# STM32-Nucleo-144.net
KiCad netlist of a schematic drawn in Altium Designer
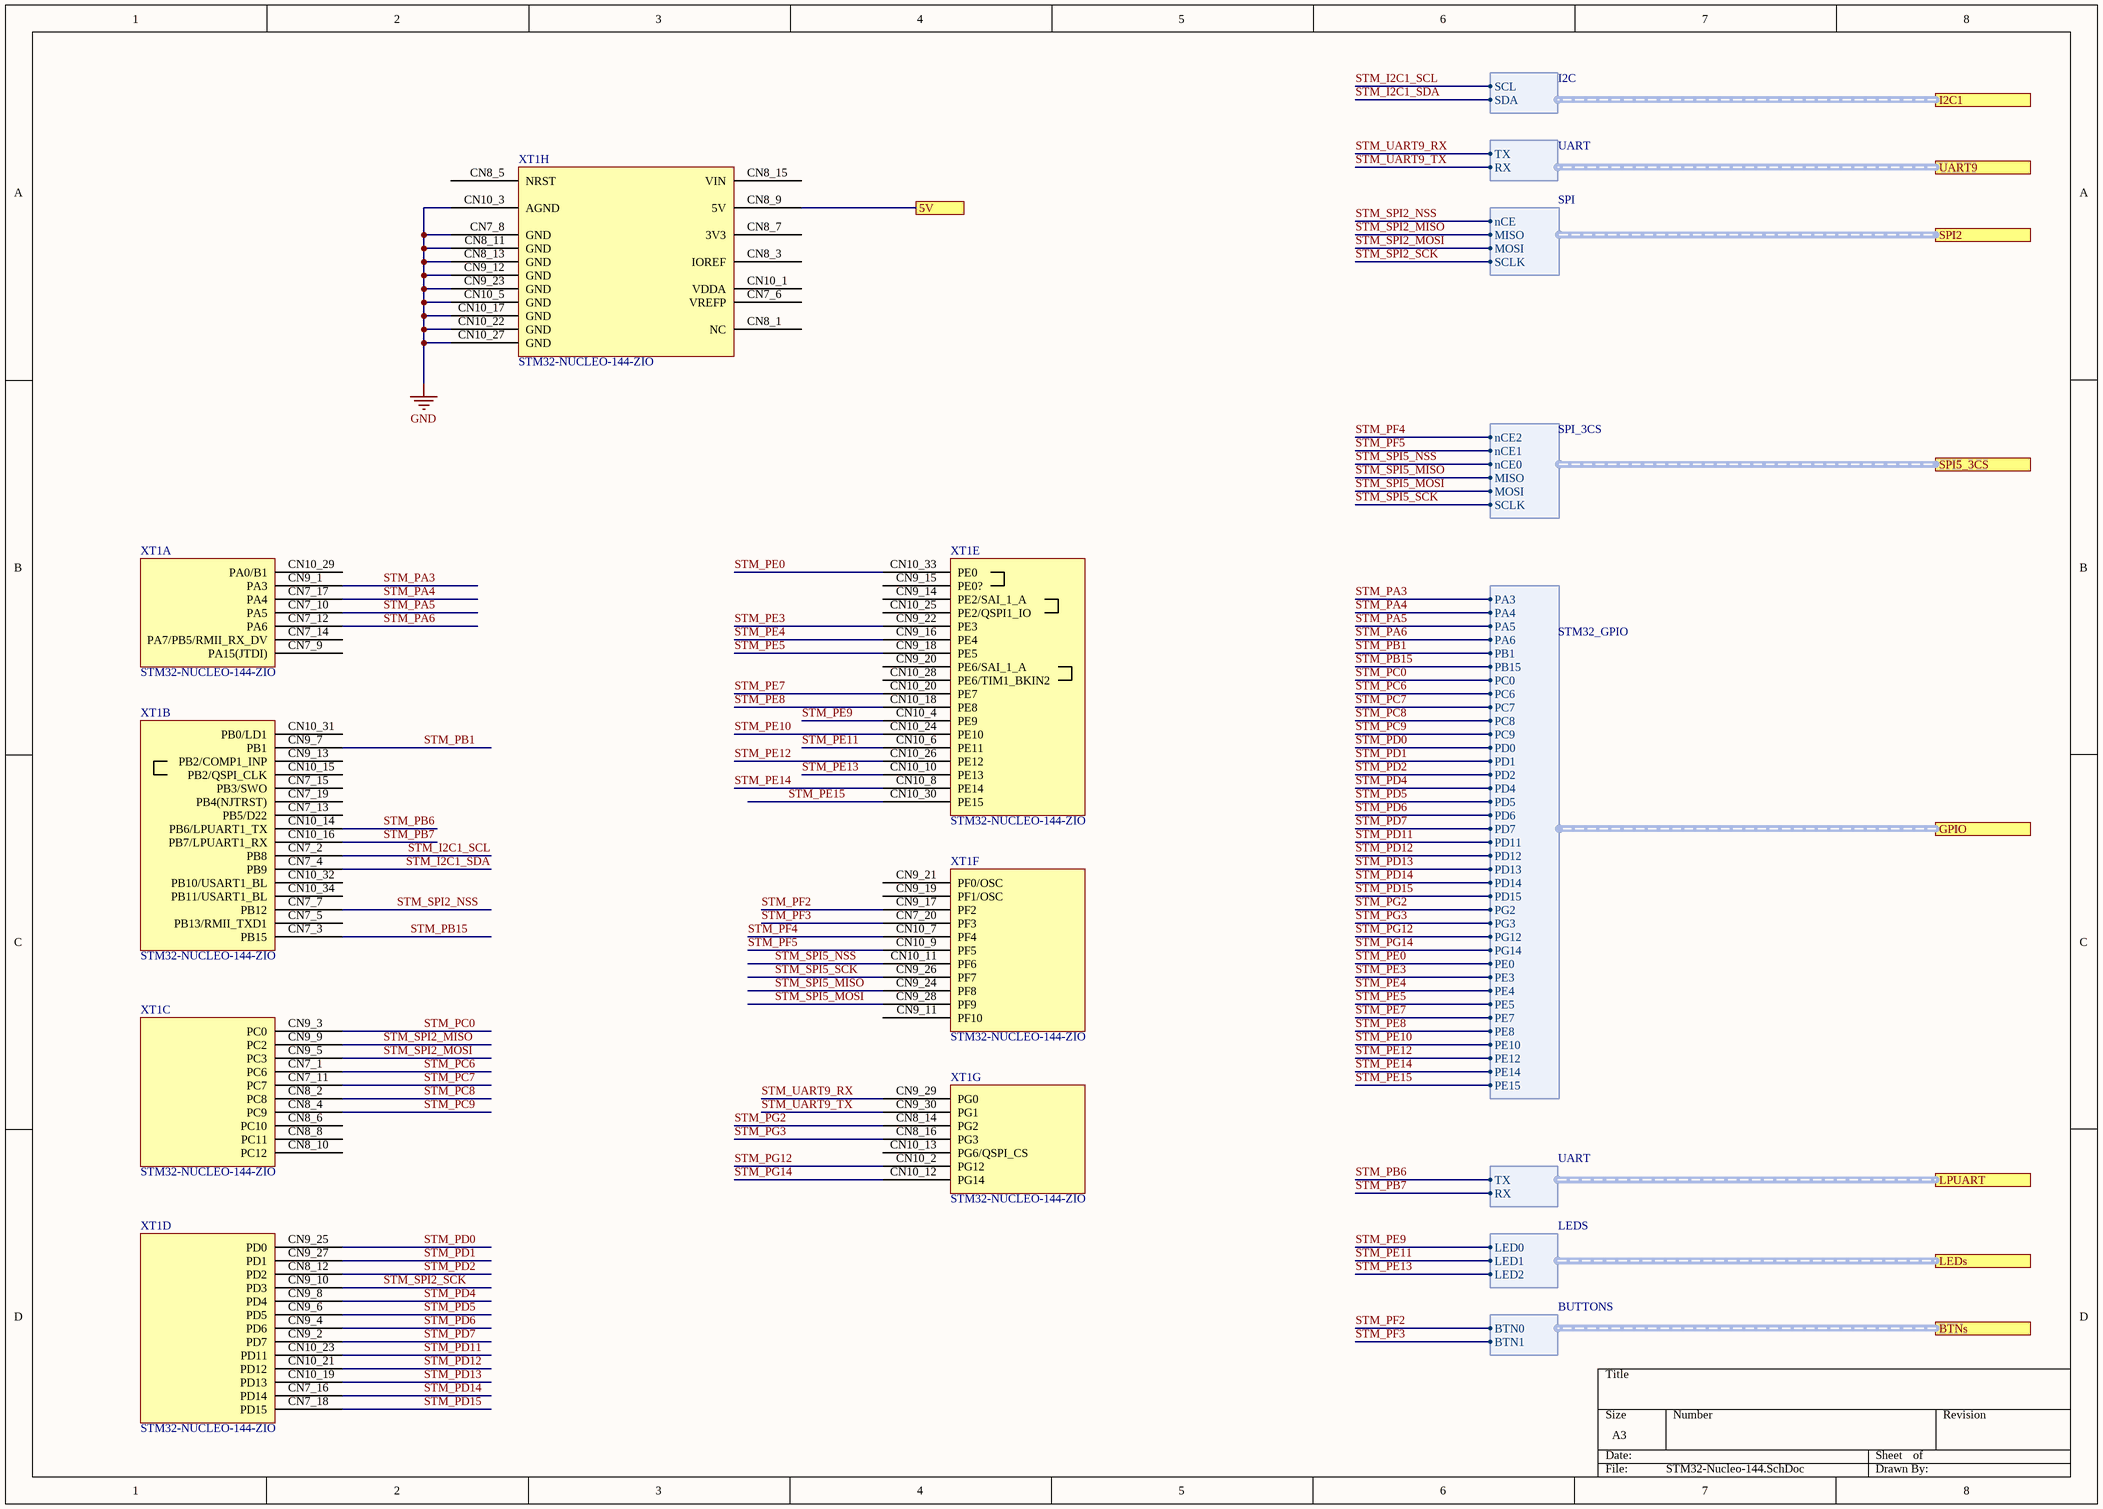
[diagram p0: STM32-Nucleo-144.SchDoc]

(export (version "E")
  (design (tool "Eeschema 10.0.6"))
  (components
    (comp (ref "XT1")
      (value "STM32-NUCLEO-144-ZIO")
      (footprint "STM32-NUCLEO-144-ZIO")
      (libsource (lib "") (part "STM32-NUCLEO-144-ZIO_2"))
    )
  )
  (nets
    (net (code "8") (name "/5V") (class "Default")
      (node (ref "XT1") (pin "CN8_9") (pinfunction "5V_CN8_9") (pintype "passive"))
    )
    (net (code "9") (name "/STM_I2C1_SCL") (class "Default")
      (node (ref "XT1") (pin "CN7_2") (pinfunction "PB8_CN7_2") (pintype "passive"))
    )
    (net (code "10") (name "/STM_I2C1_SDA") (class "Default")
      (node (ref "XT1") (pin "CN7_4") (pinfunction "PB9_CN7_4") (pintype "passive"))
    )
    (net (code "11") (name "/STM_PA3") (class "Default")
      (node (ref "XT1") (pin "CN9_1") (pinfunction "PA3_CN9_1") (pintype "passive"))
    )
    (net (code "12") (name "/STM_PA4") (class "Default")
      (node (ref "XT1") (pin "CN7_17") (pinfunction "PA4_CN7_17") (pintype "passive"))
    )
    (net (code "13") (name "/STM_PA5") (class "Default")
      (node (ref "XT1") (pin "CN7_10") (pinfunction "PA5_CN7_10") (pintype "passive"))
    )
    (net (code "14") (name "/STM_PA6") (class "Default")
      (node (ref "XT1") (pin "CN7_12") (pinfunction "PA6_CN7_12") (pintype "passive"))
    )
    (net (code "15") (name "/STM_PB1") (class "Default")
      (node (ref "XT1") (pin "CN9_7") (pinfunction "PB1_CN9_7") (pintype "passive"))
    )
    (net (code "16") (name "/STM_PB6") (class "Default")
      (node (ref "XT1") (pin "CN10_14") (pinfunction "PB6/LPUART1_TX_CN10_14") (pintype "passive"))
    )
    (net (code "17") (name "/STM_PB7") (class "Default")
      (node (ref "XT1") (pin "CN10_16") (pinfunction "PB7/LPUART1_RX_CN10_16") (pintype "passive"))
    )
    (net (code "18") (name "/STM_PB15") (class "Default")
      (node (ref "XT1") (pin "CN7_3") (pinfunction "PB15_CN7_3") (pintype "passive"))
    )
    (net (code "19") (name "/STM_PC0") (class "Default")
      (node (ref "XT1") (pin "CN9_3") (pinfunction "PC0_CN9_3") (pintype "passive"))
    )
    (net (code "20") (name "/STM_PC6") (class "Default")
      (node (ref "XT1") (pin "CN7_1") (pinfunction "PC6_CN7_1") (pintype "passive"))
    )
    (net (code "21") (name "/STM_PC7") (class "Default")
      (node (ref "XT1") (pin "CN7_11") (pinfunction "PC7_CN7_11") (pintype "passive"))
    )
    (net (code "22") (name "/STM_PC8") (class "Default")
      (node (ref "XT1") (pin "CN8_2") (pinfunction "PC8_CN8_2") (pintype "passive"))
    )
    (net (code "23") (name "/STM_PC9") (class "Default")
      (node (ref "XT1") (pin "CN8_4") (pinfunction "PC9_CN8_4") (pintype "passive"))
    )
    (net (code "24") (name "/STM_PD0") (class "Default")
      (node (ref "XT1") (pin "CN9_25") (pinfunction "PD0_CN9_25") (pintype "passive"))
    )
    (net (code "25") (name "/STM_PD1") (class "Default")
      (node (ref "XT1") (pin "CN9_27") (pinfunction "PD1_CN9_27") (pintype "passive"))
    )
    (net (code "26") (name "/STM_PD2") (class "Default")
      (node (ref "XT1") (pin "CN8_12") (pinfunction "PD2_CN8_12") (pintype "passive"))
    )
    (net (code "27") (name "/STM_PD4") (class "Default")
      (node (ref "XT1") (pin "CN9_8") (pinfunction "PD4_CN9_8") (pintype "passive"))
    )
    (net (code "28") (name "/STM_PD5") (class "Default")
      (node (ref "XT1") (pin "CN9_6") (pinfunction "PD5_CN9_6") (pintype "passive"))
    )
    (net (code "29") (name "/STM_PD6") (class "Default")
      (node (ref "XT1") (pin "CN9_4") (pinfunction "PD6_CN9_4") (pintype "passive"))
    )
    (net (code "30") (name "/STM_PD7") (class "Default")
      (node (ref "XT1") (pin "CN9_2") (pinfunction "PD7_CN9_2") (pintype "passive"))
    )
    (net (code "31") (name "/STM_PD11") (class "Default")
      (node (ref "XT1") (pin "CN10_23") (pinfunction "PD11_CN10_23") (pintype "passive"))
    )
    (net (code "32") (name "/STM_PD12") (class "Default")
      (node (ref "XT1") (pin "CN10_21") (pinfunction "PD12_CN10_21") (pintype "passive"))
    )
    (net (code "33") (name "/STM_PD13") (class "Default")
      (node (ref "XT1") (pin "CN10_19") (pinfunction "PD13_CN10_19") (pintype "passive"))
    )
    (net (code "34") (name "/STM_PD14") (class "Default")
      (node (ref "XT1") (pin "CN7_16") (pinfunction "PD14_CN7_16") (pintype "passive"))
    )
    (net (code "35") (name "/STM_PD15") (class "Default")
      (node (ref "XT1") (pin "CN7_18") (pinfunction "PD15_CN7_18") (pintype "passive"))
    )
    (net (code "36") (name "/STM_PE0") (class "Default")
      (node (ref "XT1") (pin "CN10_33") (pinfunction "PE0_CN10_33") (pintype "passive"))
    )
    (net (code "37") (name "/STM_PE3") (class "Default")
      (node (ref "XT1") (pin "CN9_22") (pinfunction "PE3_CN9_22") (pintype "passive"))
    )
    (net (code "38") (name "/STM_PE4") (class "Default")
      (node (ref "XT1") (pin "CN9_16") (pinfunction "PE4_CN9_16") (pintype "passive"))
    )
    (net (code "39") (name "/STM_PE5") (class "Default")
      (node (ref "XT1") (pin "CN9_18") (pinfunction "PE5_CN9_18") (pintype "passive"))
    )
    (net (code "40") (name "/STM_PE7") (class "Default")
      (node (ref "XT1") (pin "CN10_20") (pinfunction "PE7_CN10_20") (pintype "passive"))
    )
    (net (code "41") (name "/STM_PE8") (class "Default")
      (node (ref "XT1") (pin "CN10_18") (pinfunction "PE8_CN10_18") (pintype "passive"))
    )
    (net (code "42") (name "/STM_PE9") (class "Default")
      (node (ref "XT1") (pin "CN10_4") (pinfunction "PE9_CN10_4") (pintype "passive"))
    )
    (net (code "43") (name "/STM_PE10") (class "Default")
      (node (ref "XT1") (pin "CN10_24") (pinfunction "PE10_CN10_24") (pintype "passive"))
    )
    (net (code "44") (name "/STM_PE11") (class "Default")
      (node (ref "XT1") (pin "CN10_6") (pinfunction "PE11_CN10_6") (pintype "passive"))
    )
    (net (code "45") (name "/STM_PE12") (class "Default")
      (node (ref "XT1") (pin "CN10_26") (pinfunction "PE12_CN10_26") (pintype "passive"))
    )
    (net (code "46") (name "/STM_PE13") (class "Default")
      (node (ref "XT1") (pin "CN10_10") (pinfunction "PE13_CN10_10") (pintype "passive"))
    )
    (net (code "47") (name "/STM_PE14") (class "Default")
      (node (ref "XT1") (pin "CN10_8") (pinfunction "PE14_CN10_8") (pintype "passive"))
    )
    (net (code "48") (name "/STM_PE15") (class "Default")
      (node (ref "XT1") (pin "CN10_30") (pinfunction "PE15_CN10_30") (pintype "passive"))
    )
    (net (code "49") (name "/STM_PF2") (class "Default")
      (node (ref "XT1") (pin "CN9_17") (pinfunction "PF2_CN9_17") (pintype "passive"))
    )
    (net (code "50") (name "/STM_PF3") (class "Default")
      (node (ref "XT1") (pin "CN7_20") (pinfunction "PF3_CN7_20") (pintype "passive"))
    )
    (net (code "51") (name "/STM_PF4") (class "Default")
      (node (ref "XT1") (pin "CN10_7") (pinfunction "PF4_CN10_7") (pintype "passive"))
    )
    (net (code "52") (name "/STM_PF5") (class "Default")
      (node (ref "XT1") (pin "CN10_9") (pinfunction "PF5_CN10_9") (pintype "passive"))
    )
    (net (code "53") (name "/STM_PG2") (class "Default")
      (node (ref "XT1") (pin "CN8_14") (pinfunction "PG2_CN8_14") (pintype "passive"))
    )
    (net (code "54") (name "/STM_PG3") (class "Default")
      (node (ref "XT1") (pin "CN8_16") (pinfunction "PG3_CN8_16") (pintype "passive"))
    )
    (net (code "55") (name "/STM_PG12") (class "Default")
      (node (ref "XT1") (pin "CN10_2") (pinfunction "PG12_CN10_2") (pintype "passive"))
    )
    (net (code "56") (name "/STM_PG14") (class "Default")
      (node (ref "XT1") (pin "CN10_12") (pinfunction "PG14_CN10_12") (pintype "passive"))
    )
    (net (code "57") (name "/STM_SPI2_MISO") (class "Default")
      (node (ref "XT1") (pin "CN9_9") (pinfunction "PC2_CN9_9") (pintype "passive"))
    )
    (net (code "58") (name "/STM_SPI2_MOSI") (class "Default")
      (node (ref "XT1") (pin "CN9_5") (pinfunction "PC3_CN9_5") (pintype "passive"))
    )
    (net (code "59") (name "/STM_SPI2_NSS") (class "Default")
      (node (ref "XT1") (pin "CN7_7") (pinfunction "PB12_CN7_7") (pintype "passive"))
    )
    (net (code "60") (name "/STM_SPI2_SCK") (class "Default")
      (node (ref "XT1") (pin "CN9_10") (pinfunction "PD3_CN9_10") (pintype "passive"))
    )
    (net (code "61") (name "/STM_SPI5_MISO") (class "Default")
      (node (ref "XT1") (pin "CN9_24") (pinfunction "PF8_CN9_24") (pintype "passive"))
    )
    (net (code "62") (name "/STM_SPI5_MOSI") (class "Default")
      (node (ref "XT1") (pin "CN9_28") (pinfunction "PF9_CN9_28") (pintype "passive"))
    )
    (net (code "63") (name "/STM_SPI5_NSS") (class "Default")
      (node (ref "XT1") (pin "CN10_11") (pinfunction "PF6_CN10_11") (pintype "passive"))
    )
    (net (code "64") (name "/STM_SPI5_SCK") (class "Default")
      (node (ref "XT1") (pin "CN9_26") (pinfunction "PF7_CN9_26") (pintype "passive"))
    )
    (net (code "65") (name "/STM_UART9_RX") (class "Default")
      (node (ref "XT1") (pin "CN9_29") (pinfunction "PG0_CN9_29") (pintype "passive"))
    )
    (net (code "66") (name "/STM_UART9_TX") (class "Default")
      (node (ref "XT1") (pin "CN9_30") (pinfunction "PG1_CN9_30") (pintype "passive"))
    )
    (net (code "74") (name "GND") (class "Default")
      (node (ref "XT1") (pin "CN10_17") (pinfunction "GND_CN10_17") (pintype "passive"))
      (node (ref "XT1") (pin "CN10_22") (pinfunction "GND_CN10_22") (pintype "passive"))
      (node (ref "XT1") (pin "CN10_27") (pinfunction "GND_CN10_27") (pintype "passive"))
      (node (ref "XT1") (pin "CN10_3") (pinfunction "AGND_CN10_3") (pintype "passive"))
      (node (ref "XT1") (pin "CN10_5") (pinfunction "GND_CN10_5") (pintype "passive"))
      (node (ref "XT1") (pin "CN7_8") (pinfunction "GND_CN7_8") (pintype "passive"))
      (node (ref "XT1") (pin "CN8_11") (pinfunction "GND_CN8_11") (pintype "passive"))
      (node (ref "XT1") (pin "CN8_13") (pinfunction "GND_CN8_13") (pintype "passive"))
      (node (ref "XT1") (pin "CN9_12") (pinfunction "GND_CN9_12") (pintype "passive"))
      (node (ref "XT1") (pin "CN9_23") (pinfunction "GND_CN9_23") (pintype "passive"))
    )
    (net (code "75") (name "unconnected-(XT1A-PA0{slash}B1-PadCN10_29)") (class "Default")
      (node (ref "XT1") (pin "CN10_29") (pinfunction "PA0/B1_CN10_29") (pintype "passive"))
    )
    (net (code "76") (name "unconnected-(XT1A-PA7{slash}PB5{slash}RMII_RX_DV-PadCN7_14)") (class "Default")
      (node (ref "XT1") (pin "CN7_14") (pinfunction "PA7/PB5/RMII_RX_DV_CN7_14") (pintype "passive"))
    )
    (net (code "77") (name "unconnected-(XT1A-PA15(JTDI)-PadCN7_9)") (class "Default")
      (node (ref "XT1") (pin "CN7_9") (pinfunction "PA15(JTDI)_CN7_9") (pintype "passive"))
    )
    (net (code "78") (name "unconnected-(XT1B-PB0{slash}LD1-PadCN10_31)") (class "Default")
      (node (ref "XT1") (pin "CN10_31") (pinfunction "PB0/LD1_CN10_31") (pintype "passive"))
    )
    (net (code "79") (name "unconnected-(XT1B-PB2{slash}COMP1_INP-PadCN9_13)") (class "Default")
      (node (ref "XT1") (pin "CN9_13") (pinfunction "PB2/COMP1_INP_CN9_13") (pintype "passive"))
    )
    (net (code "80") (name "unconnected-(XT1B-PB2{slash}QSPI_CLK-PadCN10_15)") (class "Default")
      (node (ref "XT1") (pin "CN10_15") (pinfunction "PB2/QSPI_CLK_CN10_15") (pintype "passive"))
    )
    (net (code "81") (name "unconnected-(XT1B-PB3{slash}SWO-PadCN7_15)") (class "Default")
      (node (ref "XT1") (pin "CN7_15") (pinfunction "PB3/SWO_CN7_15") (pintype "passive"))
    )
    (net (code "82") (name "unconnected-(XT1B-PB4(NJTRST)-PadCN7_19)") (class "Default")
      (node (ref "XT1") (pin "CN7_19") (pinfunction "PB4(NJTRST)_CN7_19") (pintype "passive"))
    )
    (net (code "83") (name "unconnected-(XT1B-PB5{slash}D22-PadCN7_13)") (class "Default")
      (node (ref "XT1") (pin "CN7_13") (pinfunction "PB5/D22_CN7_13") (pintype "passive"))
    )
    (net (code "84") (name "unconnected-(XT1B-PB10{slash}USART1_BL-PadCN10_32)") (class "Default")
      (node (ref "XT1") (pin "CN10_32") (pinfunction "PB10/USART1_BL_CN10_32") (pintype "passive"))
    )
    (net (code "85") (name "unconnected-(XT1B-PB11{slash}USART1_BL-PadCN10_34)") (class "Default")
      (node (ref "XT1") (pin "CN10_34") (pinfunction "PB11/USART1_BL_CN10_34") (pintype "passive"))
    )
    (net (code "86") (name "unconnected-(XT1B-PB13{slash}RMII_TXD1-PadCN7_5)") (class "Default")
      (node (ref "XT1") (pin "CN7_5") (pinfunction "PB13/RMII_TXD1_CN7_5") (pintype "passive"))
    )
    (net (code "87") (name "unconnected-(XT1C-PC10-PadCN8_6)") (class "Default")
      (node (ref "XT1") (pin "CN8_6") (pinfunction "PC10_CN8_6") (pintype "passive"))
    )
    (net (code "88") (name "unconnected-(XT1C-PC11-PadCN8_8)") (class "Default")
      (node (ref "XT1") (pin "CN8_8") (pinfunction "PC11_CN8_8") (pintype "passive"))
    )
    (net (code "89") (name "unconnected-(XT1C-PC12-PadCN8_10)") (class "Default")
      (node (ref "XT1") (pin "CN8_10") (pinfunction "PC12_CN8_10") (pintype "passive"))
    )
    (net (code "90") (name "unconnected-(XT1E-PE0?-PadCN9_15)") (class "Default")
      (node (ref "XT1") (pin "CN9_15") (pinfunction "PE0?_CN9_15") (pintype "passive"))
    )
    (net (code "91") (name "unconnected-(XT1E-PE2{slash}QSPI1_IO-PadCN10_25)") (class "Default")
      (node (ref "XT1") (pin "CN10_25") (pinfunction "PE2/QSPI1_IO_CN10_25") (pintype "passive"))
    )
    (net (code "92") (name "unconnected-(XT1E-PE2{slash}SAI_1_A-PadCN9_14)") (class "Default")
      (node (ref "XT1") (pin "CN9_14") (pinfunction "PE2/SAI_1_A_CN9_14") (pintype "passive"))
    )
    (net (code "93") (name "unconnected-(XT1E-PE6{slash}SAI_1_A-PadCN9_20)") (class "Default")
      (node (ref "XT1") (pin "CN9_20") (pinfunction "PE6/SAI_1_A_CN9_20") (pintype "passive"))
    )
    (net (code "94") (name "unconnected-(XT1E-PE6{slash}TIM1_BKIN2-PadCN10_28)") (class "Default")
      (node (ref "XT1") (pin "CN10_28") (pinfunction "PE6/TIM1_BKIN2_CN10_28") (pintype "passive"))
    )
    (net (code "95") (name "unconnected-(XT1F-PF0{slash}OSC-PadCN9_21)") (class "Default")
      (node (ref "XT1") (pin "CN9_21") (pinfunction "PF0/OSC_CN9_21") (pintype "passive"))
    )
    (net (code "96") (name "unconnected-(XT1F-PF1{slash}OSC-PadCN9_19)") (class "Default")
      (node (ref "XT1") (pin "CN9_19") (pinfunction "PF1/OSC_CN9_19") (pintype "passive"))
    )
    (net (code "97") (name "unconnected-(XT1F-PF10-PadCN9_11)") (class "Default")
      (node (ref "XT1") (pin "CN9_11") (pinfunction "PF10_CN9_11") (pintype "passive"))
    )
    (net (code "98") (name "unconnected-(XT1G-PG6{slash}QSPI_CS-PadCN10_13)") (class "Default")
      (node (ref "XT1") (pin "CN10_13") (pinfunction "PG6/QSPI_CS_CN10_13") (pintype "passive"))
    )
    (net (code "99") (name "unconnected-(XT1H-3V3-PadCN8_7)") (class "Default")
      (node (ref "XT1") (pin "CN8_7") (pinfunction "3V3_CN8_7") (pintype "passive"))
    )
    (net (code "100") (name "unconnected-(XT1H-IOREF-PadCN8_3)") (class "Default")
      (node (ref "XT1") (pin "CN8_3") (pinfunction "IOREF_CN8_3") (pintype "passive"))
    )
    (net (code "101") (name "unconnected-(XT1H-NC-PadCN8_1)") (class "Default")
      (node (ref "XT1") (pin "CN8_1") (pinfunction "NC_CN8_1") (pintype "passive"))
    )
    (net (code "102") (name "unconnected-(XT1H-NRST-PadCN8_5)") (class "Default")
      (node (ref "XT1") (pin "CN8_5") (pinfunction "NRST_CN8_5") (pintype "passive"))
    )
    (net (code "103") (name "unconnected-(XT1H-VDDA-PadCN10_1)") (class "Default")
      (node (ref "XT1") (pin "CN10_1") (pinfunction "VDDA_CN10_1") (pintype "passive"))
    )
    (net (code "104") (name "unconnected-(XT1H-VIN-PadCN8_15)") (class "Default")
      (node (ref "XT1") (pin "CN8_15") (pinfunction "VIN_CN8_15") (pintype "passive"))
    )
    (net (code "105") (name "unconnected-(XT1H-VREFP-PadCN7_6)") (class "Default")
      (node (ref "XT1") (pin "CN7_6") (pinfunction "VREFP_CN7_6") (pintype "passive"))
    )
  )
)
